# touch-2ch-v4.net
KiCad netlist of a schematic drawn in Altium Designer
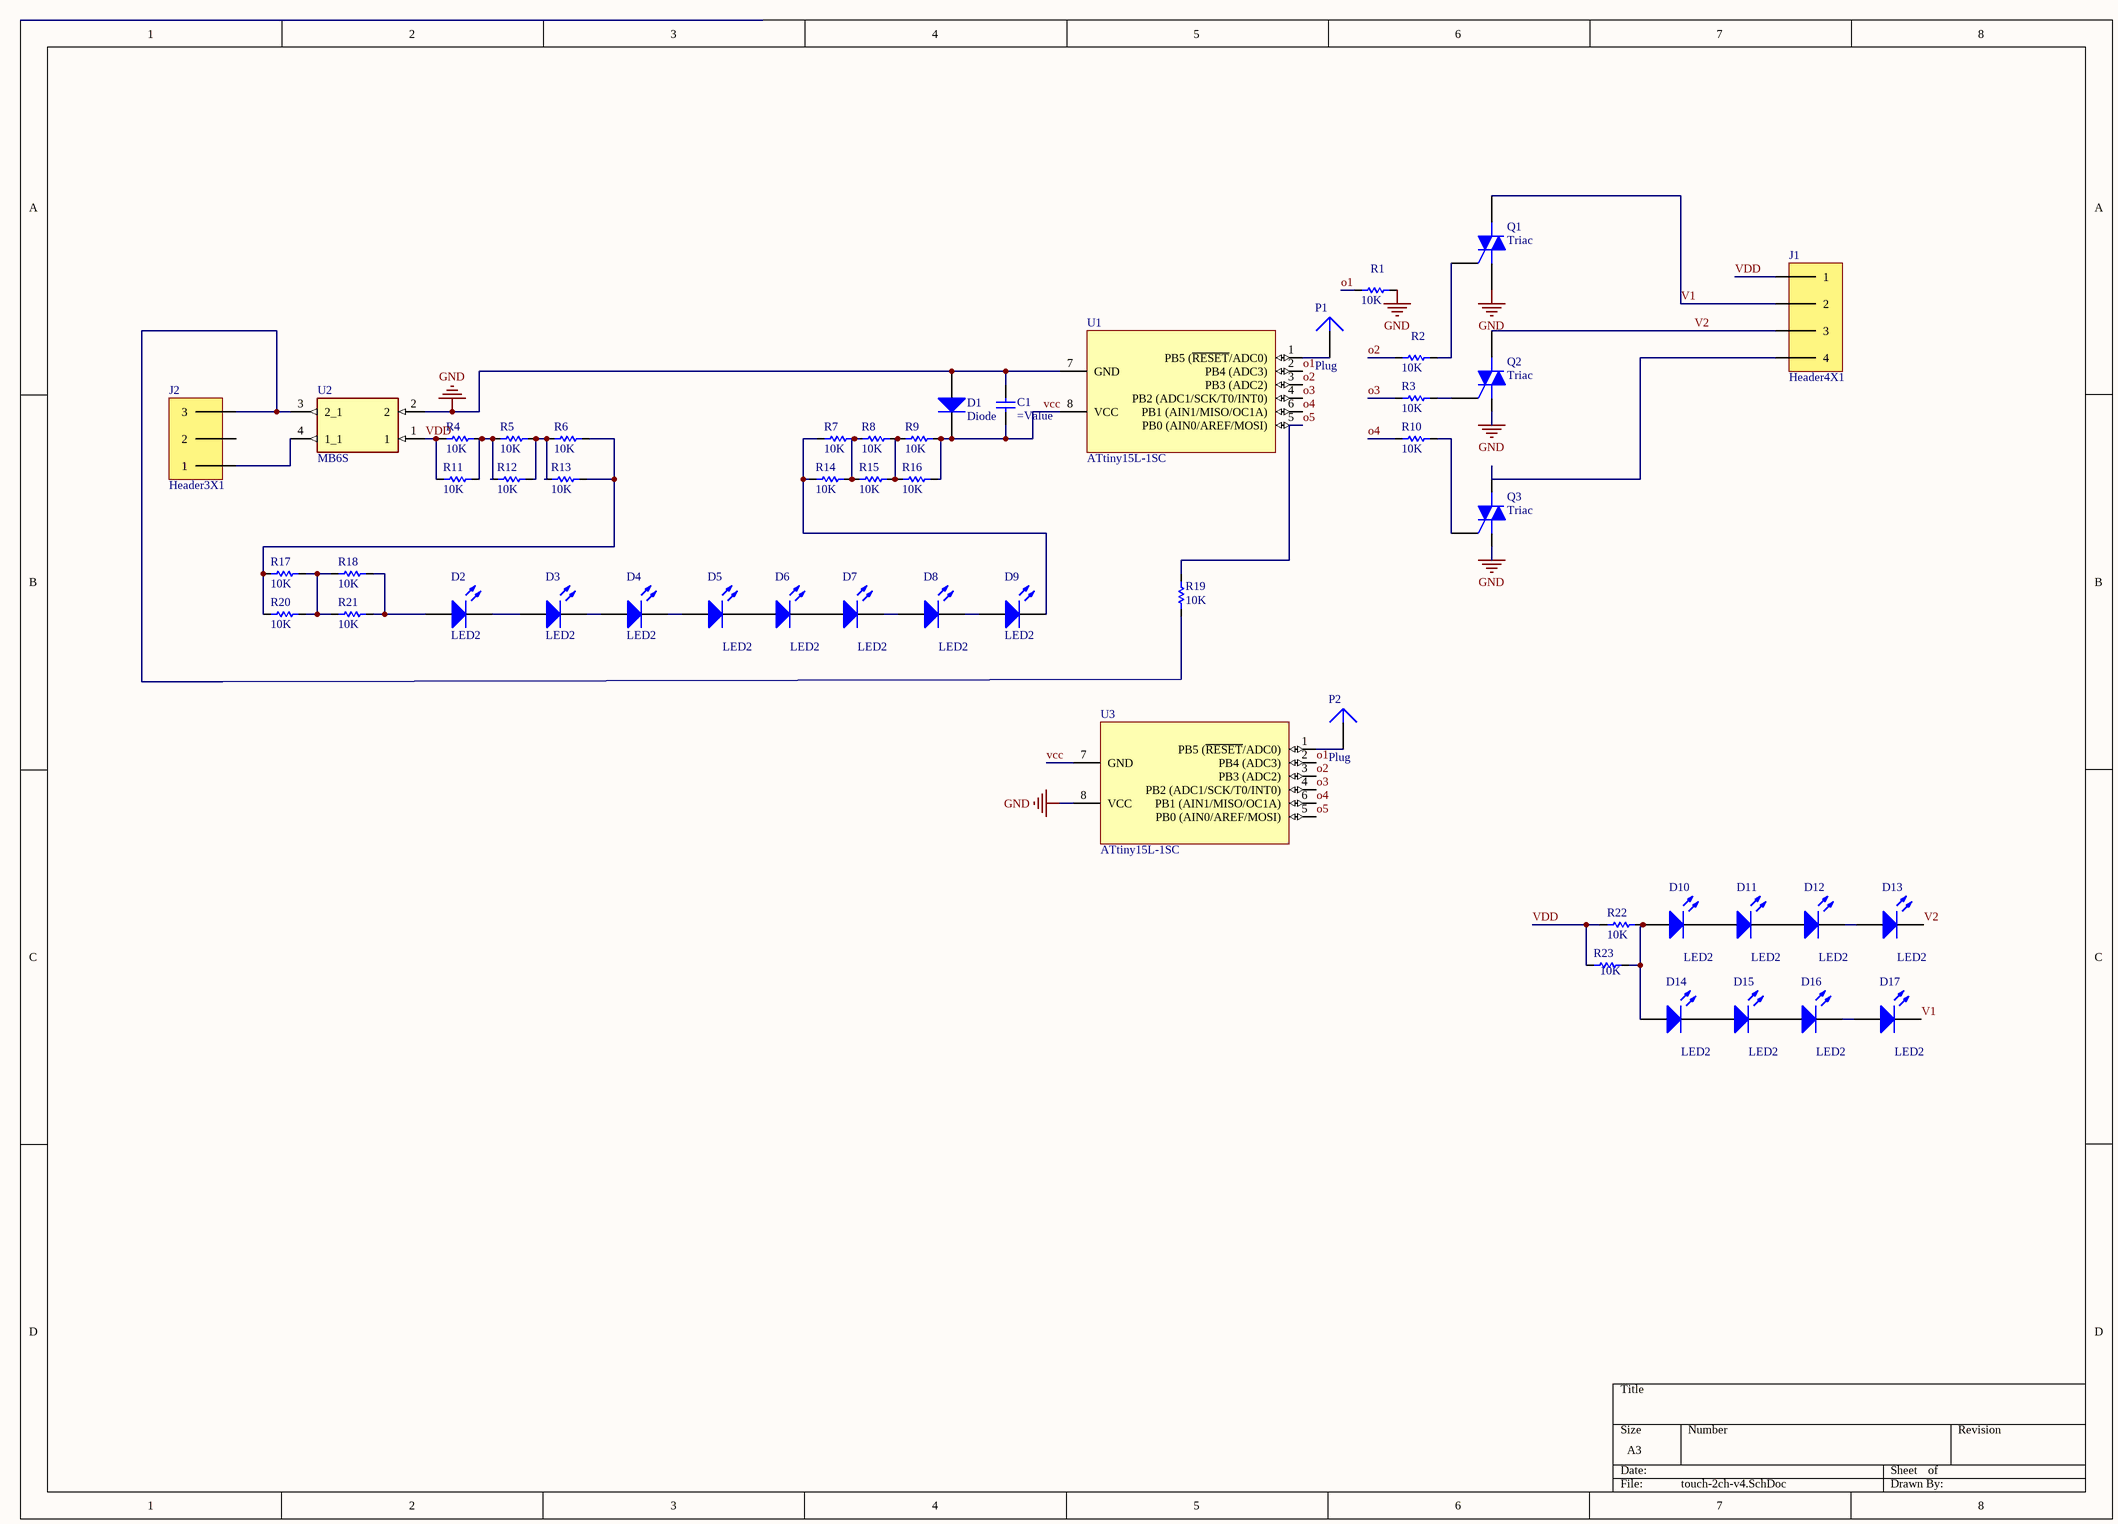
[diagram p0: touch-2ch-v4.SchDoc]

(export (version "E")
  (design (tool "Eeschema 10.0.6"))
  (components
    (comp (ref "C1")
      (value "~")
      (footprint "CAP 1206")
      (description "Capacitor")
      (libsource (lib "AltiumLib1") (part "Capacitor"))
    )
    (comp (ref "D1")
      (value "Diode")
      (footprint "C1206")
      (description "Default Diode")
      (fields (field (name "PUBLISHER") "Altium Limited"))
      (libsource (lib "Miscellaneous Devices") (part "Diode"))
    )
    (comp (ref "D2")
      (value "LED2")
      (footprint "3.2X1.6X1.1")
      (description "Typical RED, GREEN, YELLOW, AMBER GaAs LED")
      (fields (field (name "PUBLISHER") "Altium Limited"))
      (libsource (lib "Miscellaneous Devices") (part "LED2"))
    )
    (comp (ref "D3")
      (value "LED2")
      (footprint "3.2X1.6X1.1")
      (description "Typical RED, GREEN, YELLOW, AMBER GaAs LED")
      (fields (field (name "PUBLISHER") "Altium Limited"))
      (libsource (lib "Miscellaneous Devices") (part "LED2"))
    )
    (comp (ref "D4")
      (value "LED2")
      (footprint "3.2X1.6X1.1")
      (description "Typical RED, GREEN, YELLOW, AMBER GaAs LED")
      (fields (field (name "PUBLISHER") "Altium Limited"))
      (libsource (lib "Miscellaneous Devices") (part "LED2"))
    )
    (comp (ref "D5")
      (value "LED2")
      (footprint "3.2X1.6X1.1")
      (description "Typical RED, GREEN, YELLOW, AMBER GaAs LED")
      (fields (field (name "PUBLISHER") "Altium Limited"))
      (libsource (lib "Miscellaneous Devices") (part "LED2"))
    )
    (comp (ref "D6")
      (value "LED2")
      (footprint "3.2X1.6X1.1")
      (description "Typical RED, GREEN, YELLOW, AMBER GaAs LED")
      (fields (field (name "PUBLISHER") "Altium Limited"))
      (libsource (lib "Miscellaneous Devices") (part "LED2"))
    )
    (comp (ref "D7")
      (value "LED2")
      (footprint "3.2X1.6X1.1")
      (description "Typical RED, GREEN, YELLOW, AMBER GaAs LED")
      (fields (field (name "PUBLISHER") "Altium Limited"))
      (libsource (lib "Miscellaneous Devices") (part "LED2"))
    )
    (comp (ref "D8")
      (value "LED2")
      (footprint "3.2X1.6X1.1")
      (description "Typical RED, GREEN, YELLOW, AMBER GaAs LED")
      (fields (field (name "PUBLISHER") "Altium Limited"))
      (libsource (lib "Miscellaneous Devices") (part "LED2"))
    )
    (comp (ref "D9")
      (value "LED2")
      (footprint "3.2X1.6X1.1")
      (description "Typical RED, GREEN, YELLOW, AMBER GaAs LED")
      (fields (field (name "PUBLISHER") "Altium Limited"))
      (libsource (lib "Miscellaneous Devices") (part "LED2"))
    )
    (comp (ref "D10")
      (value "LED2")
      (footprint "3.2X1.6X1.1")
      (description "Typical RED, GREEN, YELLOW, AMBER GaAs LED")
      (fields (field (name "PUBLISHER") "Altium Limited"))
      (libsource (lib "Miscellaneous Devices") (part "LED2"))
    )
    (comp (ref "D11")
      (value "LED2")
      (footprint "3.2X1.6X1.1")
      (description "Typical RED, GREEN, YELLOW, AMBER GaAs LED")
      (fields (field (name "PUBLISHER") "Altium Limited"))
      (libsource (lib "Miscellaneous Devices") (part "LED2"))
    )
    (comp (ref "D12")
      (value "LED2")
      (footprint "3.2X1.6X1.1")
      (description "Typical RED, GREEN, YELLOW, AMBER GaAs LED")
      (fields (field (name "PUBLISHER") "Altium Limited"))
      (libsource (lib "Miscellaneous Devices") (part "LED2"))
    )
    (comp (ref "D13")
      (value "LED2")
      (footprint "3.2X1.6X1.1")
      (description "Typical RED, GREEN, YELLOW, AMBER GaAs LED")
      (fields (field (name "PUBLISHER") "Altium Limited"))
      (libsource (lib "Miscellaneous Devices") (part "LED2"))
    )
    (comp (ref "D14")
      (value "LED2")
      (footprint "3.2X1.6X1.1")
      (description "Typical RED, GREEN, YELLOW, AMBER GaAs LED")
      (fields (field (name "PUBLISHER") "Altium Limited"))
      (libsource (lib "Miscellaneous Devices") (part "LED2"))
    )
    (comp (ref "D15")
      (value "LED2")
      (footprint "3.2X1.6X1.1")
      (description "Typical RED, GREEN, YELLOW, AMBER GaAs LED")
      (fields (field (name "PUBLISHER") "Altium Limited"))
      (libsource (lib "Miscellaneous Devices") (part "LED2"))
    )
    (comp (ref "D16")
      (value "LED2")
      (footprint "3.2X1.6X1.1")
      (description "Typical RED, GREEN, YELLOW, AMBER GaAs LED")
      (fields (field (name "PUBLISHER") "Altium Limited"))
      (libsource (lib "Miscellaneous Devices") (part "LED2"))
    )
    (comp (ref "D17")
      (value "LED2")
      (footprint "3.2X1.6X1.1")
      (description "Typical RED, GREEN, YELLOW, AMBER GaAs LED")
      (fields (field (name "PUBLISHER") "Altium Limited"))
      (libsource (lib "Miscellaneous Devices") (part "LED2"))
    )
    (comp (ref "J1")
      (value "Header4X1")
      (footprint "HEADER 4X1")
      (libsource (lib "AltiumLib1") (part "Header4X1"))
    )
    (comp (ref "J2")
      (value "Header3X1")
      (footprint "HEADER 3X1")
      (libsource (lib "AltiumLib1") (part "Header3X1"))
    )
    (comp (ref "P1")
      (value "Plug")
      (footprint "PIN1")
      (fields (field (name "PUBLISHER") "Altium Limited"))
      (libsource (lib "Miscellaneous Connectors") (part "Plug"))
    )
    (comp (ref "P2")
      (value "Plug")
      (footprint "PIN1")
      (fields (field (name "PUBLISHER") "Altium Limited"))
      (libsource (lib "Miscellaneous Connectors") (part "Plug"))
    )
    (comp (ref "Q1")
      (value "Triac")
      (footprint "SOT89N")
      (description "Silicon Bidirectional Triode Thyristor")
      (fields (field (name "PUBLISHER") "Altium Limited"))
      (libsource (lib "Miscellaneous Devices") (part "Triac"))
    )
    (comp (ref "Q2")
      (value "Triac")
      (footprint "SOT89N")
      (description "Silicon Bidirectional Triode Thyristor")
      (fields (field (name "PUBLISHER") "Altium Limited"))
      (libsource (lib "Miscellaneous Devices") (part "Triac"))
    )
    (comp (ref "Q3")
      (value "Triac")
      (footprint "SOT89N")
      (description "Silicon Bidirectional Triode Thyristor")
      (fields (field (name "PUBLISHER") "Altium Limited"))
      (libsource (lib "Miscellaneous Devices") (part "Triac"))
    )
    (comp (ref "R1")
      (value "10K")
      (footprint "RES 1206 (3216X08L)")
      (description "Resistor")
      (fields (field (name "TOLERANCE") "5%") (field (name "POWER") "1/4 W"))
      (libsource (lib "AltiumLib1") (part "Resistor"))
    )
    (comp (ref "R2")
      (value "10K")
      (footprint "RES 1206 (3216X08L)")
      (description "Resistor")
      (fields (field (name "TOLERANCE") "5%") (field (name "POWER") "1/4 W"))
      (libsource (lib "AltiumLib1") (part "Resistor"))
    )
    (comp (ref "R3")
      (value "10K")
      (footprint "RES 1206 (3216X08L)")
      (description "Resistor")
      (fields (field (name "TOLERANCE") "5%") (field (name "POWER") "1/4 W"))
      (libsource (lib "AltiumLib1") (part "Resistor"))
    )
    (comp (ref "R4")
      (value "10K")
      (footprint "RES 1206 (3216X08L)")
      (description "Resistor")
      (fields (field (name "TOLERANCE") "5%") (field (name "POWER") "1/4 W"))
      (libsource (lib "AltiumLib1") (part "Resistor"))
    )
    (comp (ref "R5")
      (value "10K")
      (footprint "RES 1206 (3216X08L)")
      (description "Resistor")
      (fields (field (name "TOLERANCE") "5%") (field (name "POWER") "1/4 W"))
      (libsource (lib "AltiumLib1") (part "Resistor"))
    )
    (comp (ref "R6")
      (value "10K")
      (footprint "RES 1206 (3216X08L)")
      (description "Resistor")
      (fields (field (name "TOLERANCE") "5%") (field (name "POWER") "1/4 W"))
      (libsource (lib "AltiumLib1") (part "Resistor"))
    )
    (comp (ref "R7")
      (value "10K")
      (footprint "RES 1206 (3216X08L)")
      (description "Resistor")
      (fields (field (name "TOLERANCE") "5%") (field (name "POWER") "1/4 W"))
      (libsource (lib "AltiumLib1") (part "Resistor"))
    )
    (comp (ref "R8")
      (value "10K")
      (footprint "RES 1206 (3216X08L)")
      (description "Resistor")
      (fields (field (name "TOLERANCE") "5%") (field (name "POWER") "1/4 W"))
      (libsource (lib "AltiumLib1") (part "Resistor"))
    )
    (comp (ref "R9")
      (value "10K")
      (footprint "RES 1206 (3216X08L)")
      (description "Resistor")
      (fields (field (name "TOLERANCE") "5%") (field (name "POWER") "1/4 W"))
      (libsource (lib "AltiumLib1") (part "Resistor"))
    )
    (comp (ref "R10")
      (value "10K")
      (footprint "RES 1206 (3216X08L)")
      (description "Resistor")
      (fields (field (name "TOLERANCE") "5%") (field (name "POWER") "1/4 W"))
      (libsource (lib "AltiumLib1") (part "Resistor"))
    )
    (comp (ref "R11")
      (value "10K")
      (footprint "RES 1206 (3216X08L)")
      (description "Resistor")
      (fields (field (name "TOLERANCE") "5%") (field (name "POWER") "1/4 W"))
      (libsource (lib "AltiumLib1") (part "Resistor"))
    )
    (comp (ref "R12")
      (value "10K")
      (footprint "RES 1206 (3216X08L)")
      (description "Resistor")
      (fields (field (name "TOLERANCE") "5%") (field (name "POWER") "1/4 W"))
      (libsource (lib "AltiumLib1") (part "Resistor"))
    )
    (comp (ref "R13")
      (value "10K")
      (footprint "RES 1206 (3216X08L)")
      (description "Resistor")
      (fields (field (name "TOLERANCE") "5%") (field (name "POWER") "1/4 W"))
      (libsource (lib "AltiumLib1") (part "Resistor"))
    )
    (comp (ref "R14")
      (value "10K")
      (footprint "RES 1206 (3216X08L)")
      (description "Resistor")
      (fields (field (name "TOLERANCE") "5%") (field (name "POWER") "1/4 W"))
      (libsource (lib "AltiumLib1") (part "Resistor"))
    )
    (comp (ref "R15")
      (value "10K")
      (footprint "RES 1206 (3216X08L)")
      (description "Resistor")
      (fields (field (name "TOLERANCE") "5%") (field (name "POWER") "1/4 W"))
      (libsource (lib "AltiumLib1") (part "Resistor"))
    )
    (comp (ref "R16")
      (value "10K")
      (footprint "RES 1206 (3216X08L)")
      (description "Resistor")
      (fields (field (name "TOLERANCE") "5%") (field (name "POWER") "1/4 W"))
      (libsource (lib "AltiumLib1") (part "Resistor"))
    )
    (comp (ref "R17")
      (value "10K")
      (footprint "RES 1206 (3216X08L)")
      (description "Resistor")
      (fields (field (name "TOLERANCE") "5%") (field (name "POWER") "1/4 W"))
      (libsource (lib "AltiumLib1") (part "Resistor"))
    )
    (comp (ref "R18")
      (value "10K")
      (footprint "RES 1206 (3216X08L)")
      (description "Resistor")
      (fields (field (name "TOLERANCE") "5%") (field (name "POWER") "1/4 W"))
      (libsource (lib "AltiumLib1") (part "Resistor"))
    )
    (comp (ref "R19")
      (value "10K")
      (footprint "RES 1206 (3216X08L)")
      (description "Resistor")
      (fields (field (name "TOLERANCE") "5%") (field (name "POWER") "1/4 W"))
      (libsource (lib "AltiumLib1") (part "Resistor"))
    )
    (comp (ref "R20")
      (value "10K")
      (footprint "RES 1206 (3216X08L)")
      (description "Resistor")
      (fields (field (name "TOLERANCE") "5%") (field (name "POWER") "1/4 W"))
      (libsource (lib "AltiumLib1") (part "Resistor"))
    )
    (comp (ref "R21")
      (value "10K")
      (footprint "RES 1206 (3216X08L)")
      (description "Resistor")
      (fields (field (name "TOLERANCE") "5%") (field (name "POWER") "1/4 W"))
      (libsource (lib "AltiumLib1") (part "Resistor"))
    )
    (comp (ref "R22")
      (value "10K")
      (footprint "RES 1206 (3216X08L)")
      (description "Resistor")
      (fields (field (name "TOLERANCE") "5%") (field (name "POWER") "1/4 W"))
      (libsource (lib "AltiumLib1") (part "Resistor"))
    )
    (comp (ref "R23")
      (value "10K")
      (footprint "RES 1206 (3216X08L)")
      (description "Resistor")
      (fields (field (name "TOLERANCE") "5%") (field (name "POWER") "1/4 W"))
      (libsource (lib "AltiumLib1") (part "Resistor"))
    )
    (comp (ref "U1")
      (value "ATtiny15L-1SC")
      (footprint "8S2_N")
      (description "8-Bit AVR Microcontroller with 1K Byte of Flash Memory")
      (fields (field (name "PUBLISHER") "Altium Limited"))
      (libsource (lib "Atmel Microcontroller 8-Bit AVR") (part "ATtiny15L-1SC"))
    )
    (comp (ref "U2")
      (value "MB6S")
      (footprint "SOIC245P670X270-4N")
      (description "Bridge Rectifier Single Phase Standard 600V Surface Mount 4-SOIC")
      (fields (field (name "MF") "ON Semiconductor") (field (name "DIGI-KEY_PART_NUMBER") "MB6SCT-ND"))
      (libsource (lib "MB6S") (part "MB6S"))
    )
    (comp (ref "U3")
      (value "ATtiny15L-1SC")
      (footprint "8S2_N")
      (description "8-Bit AVR Microcontroller with 1K Byte of Flash Memory")
      (fields (field (name "PUBLISHER") "Altium Limited"))
      (libsource (lib "Atmel Microcontroller 8-Bit AVR") (part "ATtiny15L-1SC"))
    )
  )
  (nets
    (net (code "1") (name "/V1") (class "Default")
      (node (ref "D17") (pin "2") (pinfunction "K_2") (pintype "passive"))
      (node (ref "J1") (pin "2") (pinfunction "2_2") (pintype "passive"))
      (node (ref "Q1") (pin "2") (pinfunction "M2_2") (pintype "passive"))
    )
    (net (code "2") (name "/V2") (class "Default")
      (node (ref "D13") (pin "2") (pinfunction "K_2") (pintype "passive"))
      (node (ref "J1") (pin "3") (pinfunction "3_3") (pintype "passive"))
      (node (ref "Q2") (pin "2") (pinfunction "M2_2") (pintype "passive"))
    )
    (net (code "3") (name "/VDD") (class "Default")
      (node (ref "J1") (pin "1") (pinfunction "1_1") (pintype "passive"))
      (node (ref "R11") (pin "1") (pinfunction "1_1") (pintype "passive"))
      (node (ref "R22") (pin "2") (pinfunction "2_2") (pintype "passive"))
      (node (ref "R23") (pin "2") (pinfunction "2_2") (pintype "passive"))
      (node (ref "R4") (pin "1") (pinfunction "1_1") (pintype "passive"))
      (node (ref "U2") (pin "1") (pinfunction "1_1") (pintype "input"))
    )
    (net (code "4") (name "/o1") (class "Default")
      (node (ref "R1") (pin "1") (pinfunction "1_1") (pintype "passive"))
      (node (ref "U1") (pin "2") (pinfunction "PB4_(ADC3)_2") (pintype "bidirectional"))
      (node (ref "U3") (pin "2") (pinfunction "PB4_(ADC3)_2") (pintype "bidirectional"))
    )
    (net (code "5") (name "/o2") (class "Default")
      (node (ref "R2") (pin "1") (pinfunction "1_1") (pintype "passive"))
      (node (ref "U1") (pin "3") (pinfunction "PB3_(ADC2)_3") (pintype "bidirectional"))
      (node (ref "U3") (pin "3") (pinfunction "PB3_(ADC2)_3") (pintype "bidirectional"))
    )
    (net (code "6") (name "/o3") (class "Default")
      (node (ref "R3") (pin "1") (pinfunction "1_1") (pintype "passive"))
      (node (ref "U1") (pin "4") (pinfunction "PB2_(ADC1/SCK/T0/INT0)_4") (pintype "bidirectional"))
      (node (ref "U3") (pin "4") (pinfunction "PB2_(ADC1/SCK/T0/INT0)_4") (pintype "bidirectional"))
    )
    (net (code "7") (name "/o4") (class "Default")
      (node (ref "R10") (pin "1") (pinfunction "1_1") (pintype "passive"))
      (node (ref "U1") (pin "6") (pinfunction "PB1_(AIN1/MISO/OC1A)_6") (pintype "bidirectional"))
      (node (ref "U3") (pin "6") (pinfunction "PB1_(AIN1/MISO/OC1A)_6") (pintype "bidirectional"))
    )
    (net (code "8") (name "/o5") (class "Default")
      (node (ref "R19") (pin "2") (pinfunction "2_2") (pintype "passive"))
      (node (ref "U1") (pin "5") (pinfunction "PB0_(AIN0/AREF/MOSI)_5") (pintype "bidirectional"))
      (node (ref "U3") (pin "5") (pinfunction "PB0_(AIN0/AREF/MOSI)_5") (pintype "bidirectional"))
    )
    (net (code "9") (name "/vcc") (class "Default")
      (node (ref "C1") (pin "1") (pinfunction "+_1") (pintype "passive"))
      (node (ref "D1") (pin "2") (pinfunction "K_2") (pintype "passive"))
      (node (ref "R16") (pin "2") (pinfunction "2_2") (pintype "passive"))
      (node (ref "R9") (pin "2") (pinfunction "2_2") (pintype "passive"))
      (node (ref "U1") (pin "8") (pinfunction "VCC_8") (pintype "power_in"))
      (node (ref "U3") (pin "7") (pinfunction "GND_7") (pintype "power_in"))
    )
    (net (code "10") (name "GND") (class "Default")
      (node (ref "C1") (pin "2") (pinfunction "-_2") (pintype "passive"))
      (node (ref "D1") (pin "1") (pinfunction "A_1") (pintype "passive"))
      (node (ref "Q1") (pin "1") (pinfunction "M1_1") (pintype "passive"))
      (node (ref "Q2") (pin "1") (pinfunction "M1_1") (pintype "passive"))
      (node (ref "Q3") (pin "1") (pinfunction "M1_1") (pintype "passive"))
      (node (ref "R1") (pin "2") (pinfunction "2_2") (pintype "passive"))
      (node (ref "U1") (pin "7") (pinfunction "GND_7") (pintype "power_in"))
      (node (ref "U2") (pin "2") (pinfunction "2_2") (pintype "input"))
      (node (ref "U3") (pin "8") (pinfunction "VCC_8") (pintype "power_in"))
    )
    (net (code "11") (name "Net-(D2-A)") (class "Default")
      (node (ref "D2") (pin "1") (pinfunction "A_1") (pintype "passive"))
      (node (ref "R18") (pin "2") (pinfunction "2_2") (pintype "passive"))
      (node (ref "R21") (pin "2") (pinfunction "2_2") (pintype "passive"))
    )
    (net (code "12") (name "Net-(D2-K)") (class "Default")
      (node (ref "D2") (pin "2") (pinfunction "K_2") (pintype "passive"))
      (node (ref "D3") (pin "1") (pinfunction "A_1") (pintype "passive"))
    )
    (net (code "13") (name "Net-(D3-K)") (class "Default")
      (node (ref "D3") (pin "2") (pinfunction "K_2") (pintype "passive"))
      (node (ref "D4") (pin "1") (pinfunction "A_1") (pintype "passive"))
    )
    (net (code "14") (name "Net-(D4-K)") (class "Default")
      (node (ref "D4") (pin "2") (pinfunction "K_2") (pintype "passive"))
      (node (ref "D5") (pin "1") (pinfunction "A_1") (pintype "passive"))
    )
    (net (code "15") (name "Net-(D5-K)") (class "Default")
      (node (ref "D5") (pin "2") (pinfunction "K_2") (pintype "passive"))
      (node (ref "D6") (pin "1") (pinfunction "A_1") (pintype "passive"))
    )
    (net (code "16") (name "Net-(D6-K)") (class "Default")
      (node (ref "D6") (pin "2") (pinfunction "K_2") (pintype "passive"))
      (node (ref "D7") (pin "1") (pinfunction "A_1") (pintype "passive"))
    )
    (net (code "17") (name "Net-(D7-K)") (class "Default")
      (node (ref "D7") (pin "2") (pinfunction "K_2") (pintype "passive"))
      (node (ref "D8") (pin "1") (pinfunction "A_1") (pintype "passive"))
    )
    (net (code "18") (name "Net-(D8-K)") (class "Default")
      (node (ref "D8") (pin "2") (pinfunction "K_2") (pintype "passive"))
      (node (ref "D9") (pin "1") (pinfunction "A_1") (pintype "passive"))
    )
    (net (code "19") (name "Net-(D9-K)") (class "Default")
      (node (ref "D9") (pin "2") (pinfunction "K_2") (pintype "passive"))
      (node (ref "R14") (pin "1") (pinfunction "1_1") (pintype "passive"))
      (node (ref "R7") (pin "1") (pinfunction "1_1") (pintype "passive"))
    )
    (net (code "20") (name "Net-(D10-A)") (class "Default")
      (node (ref "D10") (pin "1") (pinfunction "A_1") (pintype "passive"))
      (node (ref "D14") (pin "1") (pinfunction "A_1") (pintype "passive"))
      (node (ref "R22") (pin "1") (pinfunction "1_1") (pintype "passive"))
      (node (ref "R23") (pin "1") (pinfunction "1_1") (pintype "passive"))
    )
    (net (code "21") (name "Net-(D10-K)") (class "Default")
      (node (ref "D10") (pin "2") (pinfunction "K_2") (pintype "passive"))
      (node (ref "D11") (pin "1") (pinfunction "A_1") (pintype "passive"))
    )
    (net (code "22") (name "Net-(D11-K)") (class "Default")
      (node (ref "D11") (pin "2") (pinfunction "K_2") (pintype "passive"))
      (node (ref "D12") (pin "1") (pinfunction "A_1") (pintype "passive"))
    )
    (net (code "23") (name "Net-(D12-K)") (class "Default")
      (node (ref "D12") (pin "2") (pinfunction "K_2") (pintype "passive"))
      (node (ref "D13") (pin "1") (pinfunction "A_1") (pintype "passive"))
    )
    (net (code "24") (name "Net-(D14-K)") (class "Default")
      (node (ref "D14") (pin "2") (pinfunction "K_2") (pintype "passive"))
      (node (ref "D15") (pin "1") (pinfunction "A_1") (pintype "passive"))
    )
    (net (code "25") (name "Net-(D15-K)") (class "Default")
      (node (ref "D15") (pin "2") (pinfunction "K_2") (pintype "passive"))
      (node (ref "D16") (pin "1") (pinfunction "A_1") (pintype "passive"))
    )
    (net (code "26") (name "Net-(D16-K)") (class "Default")
      (node (ref "D16") (pin "2") (pinfunction "K_2") (pintype "passive"))
      (node (ref "D17") (pin "1") (pinfunction "A_1") (pintype "passive"))
    )
    (net (code "27") (name "Net-(Q1-G)") (class "Default")
      (node (ref "Q1") (pin "3") (pinfunction "G_3") (pintype "passive"))
      (node (ref "R2") (pin "2") (pinfunction "2_2") (pintype "passive"))
    )
    (net (code "28") (name "Net-(Q2-G)") (class "Default")
      (node (ref "Q2") (pin "3") (pinfunction "G_3") (pintype "passive"))
      (node (ref "R3") (pin "2") (pinfunction "2_2") (pintype "passive"))
    )
    (net (code "29") (name "Net-(Q3-G)") (class "Default")
      (node (ref "Q3") (pin "3") (pinfunction "G_3") (pintype "passive"))
      (node (ref "R10") (pin "2") (pinfunction "2_2") (pintype "passive"))
    )
    (net (code "30") (name "Net-(Q3-M2)") (class "Default")
      (node (ref "J1") (pin "4") (pinfunction "4_4") (pintype "passive"))
      (node (ref "Q3") (pin "2") (pinfunction "M2_2") (pintype "passive"))
    )
    (net (code "31") (name "Net-(R11-Pad2)") (class "Default")
      (node (ref "R11") (pin "2") (pinfunction "2_2") (pintype "passive"))
      (node (ref "R12") (pin "1") (pinfunction "1_1") (pintype "passive"))
      (node (ref "R4") (pin "2") (pinfunction "2_2") (pintype "passive"))
      (node (ref "R5") (pin "1") (pinfunction "1_1") (pintype "passive"))
    )
    (net (code "32") (name "Net-(R12-Pad2)") (class "Default")
      (node (ref "R12") (pin "2") (pinfunction "2_2") (pintype "passive"))
      (node (ref "R13") (pin "1") (pinfunction "1_1") (pintype "passive"))
      (node (ref "R5") (pin "2") (pinfunction "2_2") (pintype "passive"))
      (node (ref "R6") (pin "1") (pinfunction "1_1") (pintype "passive"))
    )
    (net (code "33") (name "Net-(R13-Pad2)") (class "Default")
      (node (ref "R13") (pin "2") (pinfunction "2_2") (pintype "passive"))
      (node (ref "R17") (pin "1") (pinfunction "1_1") (pintype "passive"))
      (node (ref "R20") (pin "1") (pinfunction "1_1") (pintype "passive"))
      (node (ref "R6") (pin "2") (pinfunction "2_2") (pintype "passive"))
    )
    (net (code "34") (name "Net-(R14-Pad2)") (class "Default")
      (node (ref "R14") (pin "2") (pinfunction "2_2") (pintype "passive"))
      (node (ref "R15") (pin "1") (pinfunction "1_1") (pintype "passive"))
      (node (ref "R7") (pin "2") (pinfunction "2_2") (pintype "passive"))
      (node (ref "R8") (pin "1") (pinfunction "1_1") (pintype "passive"))
    )
    (net (code "35") (name "Net-(R15-Pad2)") (class "Default")
      (node (ref "R15") (pin "2") (pinfunction "2_2") (pintype "passive"))
      (node (ref "R16") (pin "1") (pinfunction "1_1") (pintype "passive"))
      (node (ref "R8") (pin "2") (pinfunction "2_2") (pintype "passive"))
      (node (ref "R9") (pin "1") (pinfunction "1_1") (pintype "passive"))
    )
    (net (code "36") (name "Net-(R17-Pad2)") (class "Default")
      (node (ref "R17") (pin "2") (pinfunction "2_2") (pintype "passive"))
      (node (ref "R18") (pin "1") (pinfunction "1_1") (pintype "passive"))
      (node (ref "R20") (pin "2") (pinfunction "2_2") (pintype "passive"))
      (node (ref "R21") (pin "1") (pinfunction "1_1") (pintype "passive"))
    )
    (net (code "37") (name "Net-(U1-PB5_(~{RESET}{slash}ADC0))") (class "Default")
      (node (ref "P1") (pin "1") (pinfunction "1_1") (pintype "passive"))
      (node (ref "U1") (pin "1") (pinfunction "PB5_(~{RESET}/ADC0)_1") (pintype "bidirectional"))
    )
    (net (code "38") (name "Net-(U2-1_1)") (class "Default")
      (node (ref "J2") (pin "1") (pinfunction "1_1") (pintype "passive"))
      (node (ref "U2") (pin "4") (pinfunction "1_1_4") (pintype "output"))
    )
    (net (code "39") (name "Net-(U2-2_1)") (class "Default")
      (node (ref "J2") (pin "3") (pinfunction "3_3") (pintype "passive"))
      (node (ref "R19") (pin "1") (pinfunction "1_1") (pintype "passive"))
      (node (ref "U2") (pin "3") (pinfunction "2_1_3") (pintype "output"))
    )
    (net (code "40") (name "Net-(U3-PB5_(~{RESET}{slash}ADC0))") (class "Default")
      (node (ref "P2") (pin "1") (pinfunction "1_1") (pintype "passive"))
      (node (ref "U3") (pin "1") (pinfunction "PB5_(~{RESET}/ADC0)_1") (pintype "bidirectional"))
    )
    (net (code "41") (name "unconnected-(J2-Pad2)") (class "Default")
      (node (ref "J2") (pin "2") (pinfunction "2_2") (pintype "passive"))
    )
  )
)
